# DiodeOR.net
KiCad netlist of a schematic drawn in EAGLE
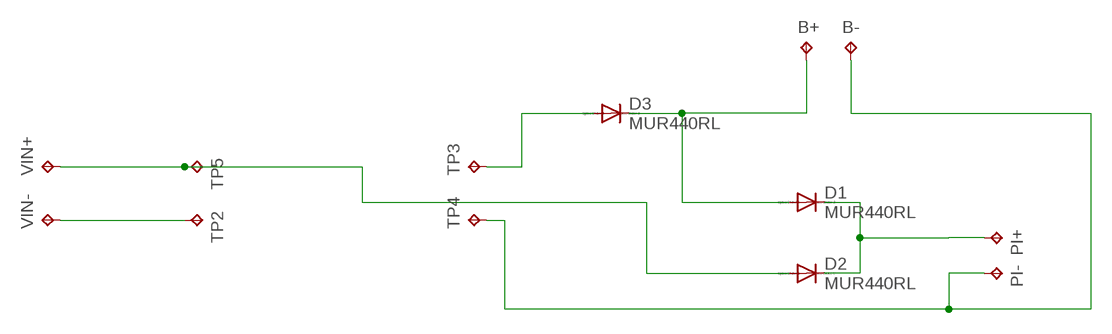
[diagram p0: schematic, sheet 1]

(export (version "E")
  (design (tool "Eeschema 10.0.6"))
  (components
    (comp (ref "B+")
      (value "TPPAD1-20Y")
      (footprint "eagle-import:P1-20Y")
      (libsource (lib "eagle-import") (part "TPPAD1-20Y"))
    )
    (comp (ref "B-")
      (value "TPPAD1-20Y")
      (footprint "eagle-import:P1-20Y")
      (libsource (lib "eagle-import") (part "TPPAD1-20Y"))
    )
    (comp (ref "D1")
      (value "MUR440RL")
      (footprint "eagle-import:C2673")
      (libsource (lib "eagle-import") (part "MUR440RL"))
    )
    (comp (ref "D2")
      (value "MUR440RL")
      (footprint "eagle-import:C2673")
      (libsource (lib "eagle-import") (part "MUR440RL"))
    )
    (comp (ref "D3")
      (value "MUR440RL")
      (footprint "eagle-import:C2673")
      (libsource (lib "eagle-import") (part "MUR440RL"))
    )
    (comp (ref "PI+")
      (value "TPPAD1-20Y")
      (footprint "eagle-import:P1-20Y")
      (libsource (lib "eagle-import") (part "TPPAD1-20Y"))
    )
    (comp (ref "PI-")
      (value "TPPAD1-20Y")
      (footprint "eagle-import:P1-20Y")
      (libsource (lib "eagle-import") (part "TPPAD1-20Y"))
    )
    (comp (ref "TP2")
      (value "TPPAD1-20Y")
      (footprint "eagle-import:P1-20Y")
      (libsource (lib "eagle-import") (part "TPPAD1-20Y"))
    )
    (comp (ref "TP3")
      (value "TPPAD1-20Y")
      (footprint "eagle-import:P1-20Y")
      (libsource (lib "eagle-import") (part "TPPAD1-20Y"))
    )
    (comp (ref "TP4")
      (value "TPPAD1-20Y")
      (footprint "eagle-import:P1-20Y")
      (libsource (lib "eagle-import") (part "TPPAD1-20Y"))
    )
    (comp (ref "TP5")
      (value "TPPAD1-20Y")
      (footprint "eagle-import:P1-20Y")
      (libsource (lib "eagle-import") (part "TPPAD1-20Y"))
    )
    (comp (ref "VIN+")
      (value "TPPAD1-20Y")
      (footprint "eagle-import:P1-20Y")
      (libsource (lib "eagle-import") (part "TPPAD1-20Y"))
    )
    (comp (ref "VIN-")
      (value "TPPAD1-20Y")
      (footprint "eagle-import:P1-20Y")
      (libsource (lib "eagle-import") (part "TPPAD1-20Y"))
    )
  )
  (nets
    (net (code "1") (name "Net-(B+-PadTP)") (class "Default")
      (node (ref "B+") (pin "TP") (pinfunction "TP_TP") (pintype "input"))
      (node (ref "D1") (pin "A") (pinfunction "A_A") (pintype "passive"))
      (node (ref "D3") (pin "C") (pinfunction "C_C") (pintype "passive"))
    )
    (net (code "2") (name "Net-(B--PadTP)") (class "Default")
      (node (ref "B-") (pin "TP") (pinfunction "TP_TP") (pintype "input"))
      (node (ref "PI-") (pin "TP") (pinfunction "TP_TP") (pintype "input"))
      (node (ref "TP4") (pin "TP") (pinfunction "TP_TP") (pintype "input"))
    )
    (net (code "3") (name "Net-(D1-PadC)") (class "Default")
      (node (ref "D1") (pin "C") (pinfunction "C_C") (pintype "passive"))
      (node (ref "D2") (pin "C") (pinfunction "C_C") (pintype "passive"))
      (node (ref "PI+") (pin "TP") (pinfunction "TP_TP") (pintype "input"))
    )
    (net (code "4") (name "Net-(D2-PadA)") (class "Default")
      (node (ref "D2") (pin "A") (pinfunction "A_A") (pintype "passive"))
      (node (ref "TP5") (pin "TP") (pinfunction "TP_TP") (pintype "input"))
      (node (ref "VIN+") (pin "TP") (pinfunction "TP_TP") (pintype "input"))
    )
    (net (code "5") (name "Net-(D3-PadA)") (class "Default")
      (node (ref "D3") (pin "A") (pinfunction "A_A") (pintype "passive"))
      (node (ref "TP3") (pin "TP") (pinfunction "TP_TP") (pintype "input"))
    )
    (net (code "6") (name "Net-(TP2-PadTP)") (class "Default")
      (node (ref "TP2") (pin "TP") (pinfunction "TP_TP") (pintype "input"))
      (node (ref "VIN-") (pin "TP") (pinfunction "TP_TP") (pintype "input"))
    )
  )
)
